# Safety_2019_V_3_0_Power_IC_s.net
KiCad netlist of a schematic drawn in Altium Designer
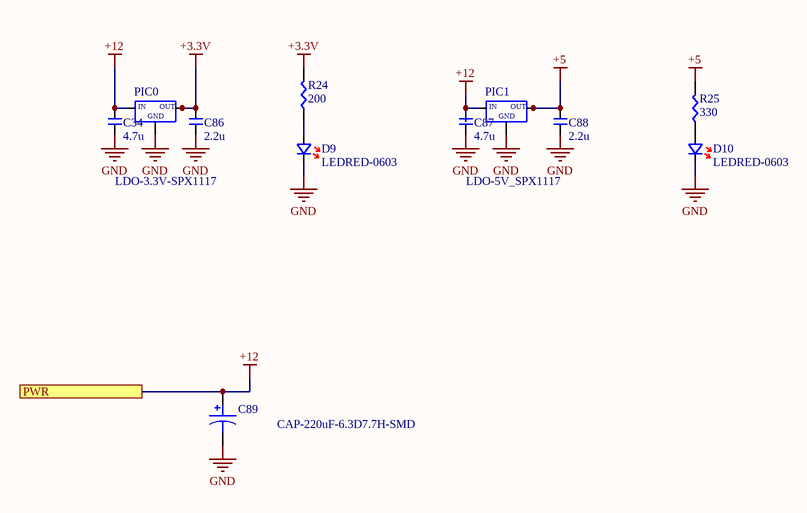
[diagram p0: Safety_2019_V_3_0_Power_IC's.SchDoc]

(export (version "E")
  (design (tool "Eeschema 10.0.6"))
  (components
    (comp (ref "C34")
      (value "4.7u")
      (footprint "CAP-0603")
      (libsource (lib "ife19_Elec_Library") (part "CAP-0603"))
    )
    (comp (ref "C86")
      (value "2.2u")
      (footprint "CAP-0603")
      (libsource (lib "ife19_Elec_Library") (part "CAP-0603"))
    )
    (comp (ref "C87")
      (value "4.7u")
      (footprint "CAP-0603")
      (libsource (lib "ife19_Elec_Library") (part "CAP-0603"))
    )
    (comp (ref "C88")
      (value "2.2u")
      (footprint "CAP-0603")
      (libsource (lib "ife19_Elec_Library") (part "CAP-0603"))
    )
    (comp (ref "C89")
      (value "CAP-220uF-6.3D7.7H-SMD")
      (footprint "CAP-6.3D7.7H-SMD")
      (libsource (lib "ife19_Elec_Library") (part "CAP-6.3D7.7H-SMD"))
    )
    (comp (ref "D9")
      (value "LEDRED-0603")
      (footprint "LEDRED-0603")
      (libsource (lib "ife19_Elec_Library") (part "LEDRED-0603"))
    )
    (comp (ref "D10")
      (value "LEDRED-0603")
      (footprint "LEDRED-0603")
      (libsource (lib "ife19_Elec_Library") (part "LEDRED-0603"))
    )
    (comp (ref "PIC0")
      (value "LDO-3.3V-SPX1117")
      (footprint "SOT223")
      (libsource (lib "ife19_Elec_Library") (part "LDO-SOT223_SPX1117"))
    )
    (comp (ref "PIC1")
      (value "LDO-5V_SPX1117")
      (footprint "SOT223")
      (libsource (lib "ife19_Elec_Library") (part "LDO-SOT223_SPX1117"))
    )
    (comp (ref "R24")
      (value "200")
      (footprint "RES-0603")
      (libsource (lib "ife19_Elec_Library") (part "RES-0603"))
    )
    (comp (ref "R25")
      (value "330")
      (footprint "RES-0603")
      (libsource (lib "ife19_Elec_Library") (part "RES-0603"))
    )
  )
  (nets
    (net (code "1") (name "+3.3V") (class "Default")
      (node (ref "C86") (pin "2") (pinfunction "2_2") (pintype "passive"))
      (node (ref "PIC0") (pin "2") (pinfunction "2_2") (pintype "passive"))
      (node (ref "PIC0") (pin "4") (pinfunction "4_4") (pintype "passive"))
      (node (ref "R24") (pin "2") (pinfunction "2_2") (pintype "passive"))
    )
    (net (code "2") (name "+5") (class "Default")
      (node (ref "C88") (pin "2") (pinfunction "2_2") (pintype "passive"))
      (node (ref "PIC1") (pin "2") (pinfunction "2_2") (pintype "passive"))
      (node (ref "PIC1") (pin "4") (pinfunction "4_4") (pintype "passive"))
      (node (ref "R25") (pin "2") (pinfunction "2_2") (pintype "passive"))
    )
    (net (code "3") (name "+12") (class "Default")
      (node (ref "C34") (pin "2") (pinfunction "2_2") (pintype "passive"))
      (node (ref "C87") (pin "2") (pinfunction "2_2") (pintype "passive"))
      (node (ref "C89") (pin "POS") (pinfunction "+_POS") (pintype "passive"))
      (node (ref "PIC0") (pin "3") (pinfunction "3_3") (pintype "passive"))
      (node (ref "PIC1") (pin "3") (pinfunction "3_3") (pintype "passive"))
    )
    (net (code "4") (name "GND") (class "Default")
      (node (ref "C34") (pin "1") (pinfunction "1_1") (pintype "passive"))
      (node (ref "C86") (pin "1") (pinfunction "1_1") (pintype "passive"))
      (node (ref "C87") (pin "1") (pinfunction "1_1") (pintype "passive"))
      (node (ref "C88") (pin "1") (pinfunction "1_1") (pintype "passive"))
      (node (ref "C89") (pin "NEG") (pinfunction "-_NEG") (pintype "passive"))
      (node (ref "D10") (pin "K") (pinfunction "K_K") (pintype "passive"))
      (node (ref "D9") (pin "K") (pinfunction "K_K") (pintype "passive"))
      (node (ref "PIC0") (pin "1") (pinfunction "1_1") (pintype "passive"))
      (node (ref "PIC1") (pin "1") (pinfunction "1_1") (pintype "passive"))
    )
    (net (code "5") (name "Net-(D9-PadA)") (class "Default")
      (node (ref "D9") (pin "A") (pinfunction "A_A") (pintype "passive"))
      (node (ref "R24") (pin "1") (pinfunction "1_1") (pintype "passive"))
    )
    (net (code "6") (name "Net-(D10-PadA)") (class "Default")
      (node (ref "D10") (pin "A") (pinfunction "A_A") (pintype "passive"))
      (node (ref "R25") (pin "1") (pinfunction "1_1") (pintype "passive"))
    )
  )
)
